# EasyEda_Node.net
KiCad netlist of a schematic drawn in EasyEDA Pro
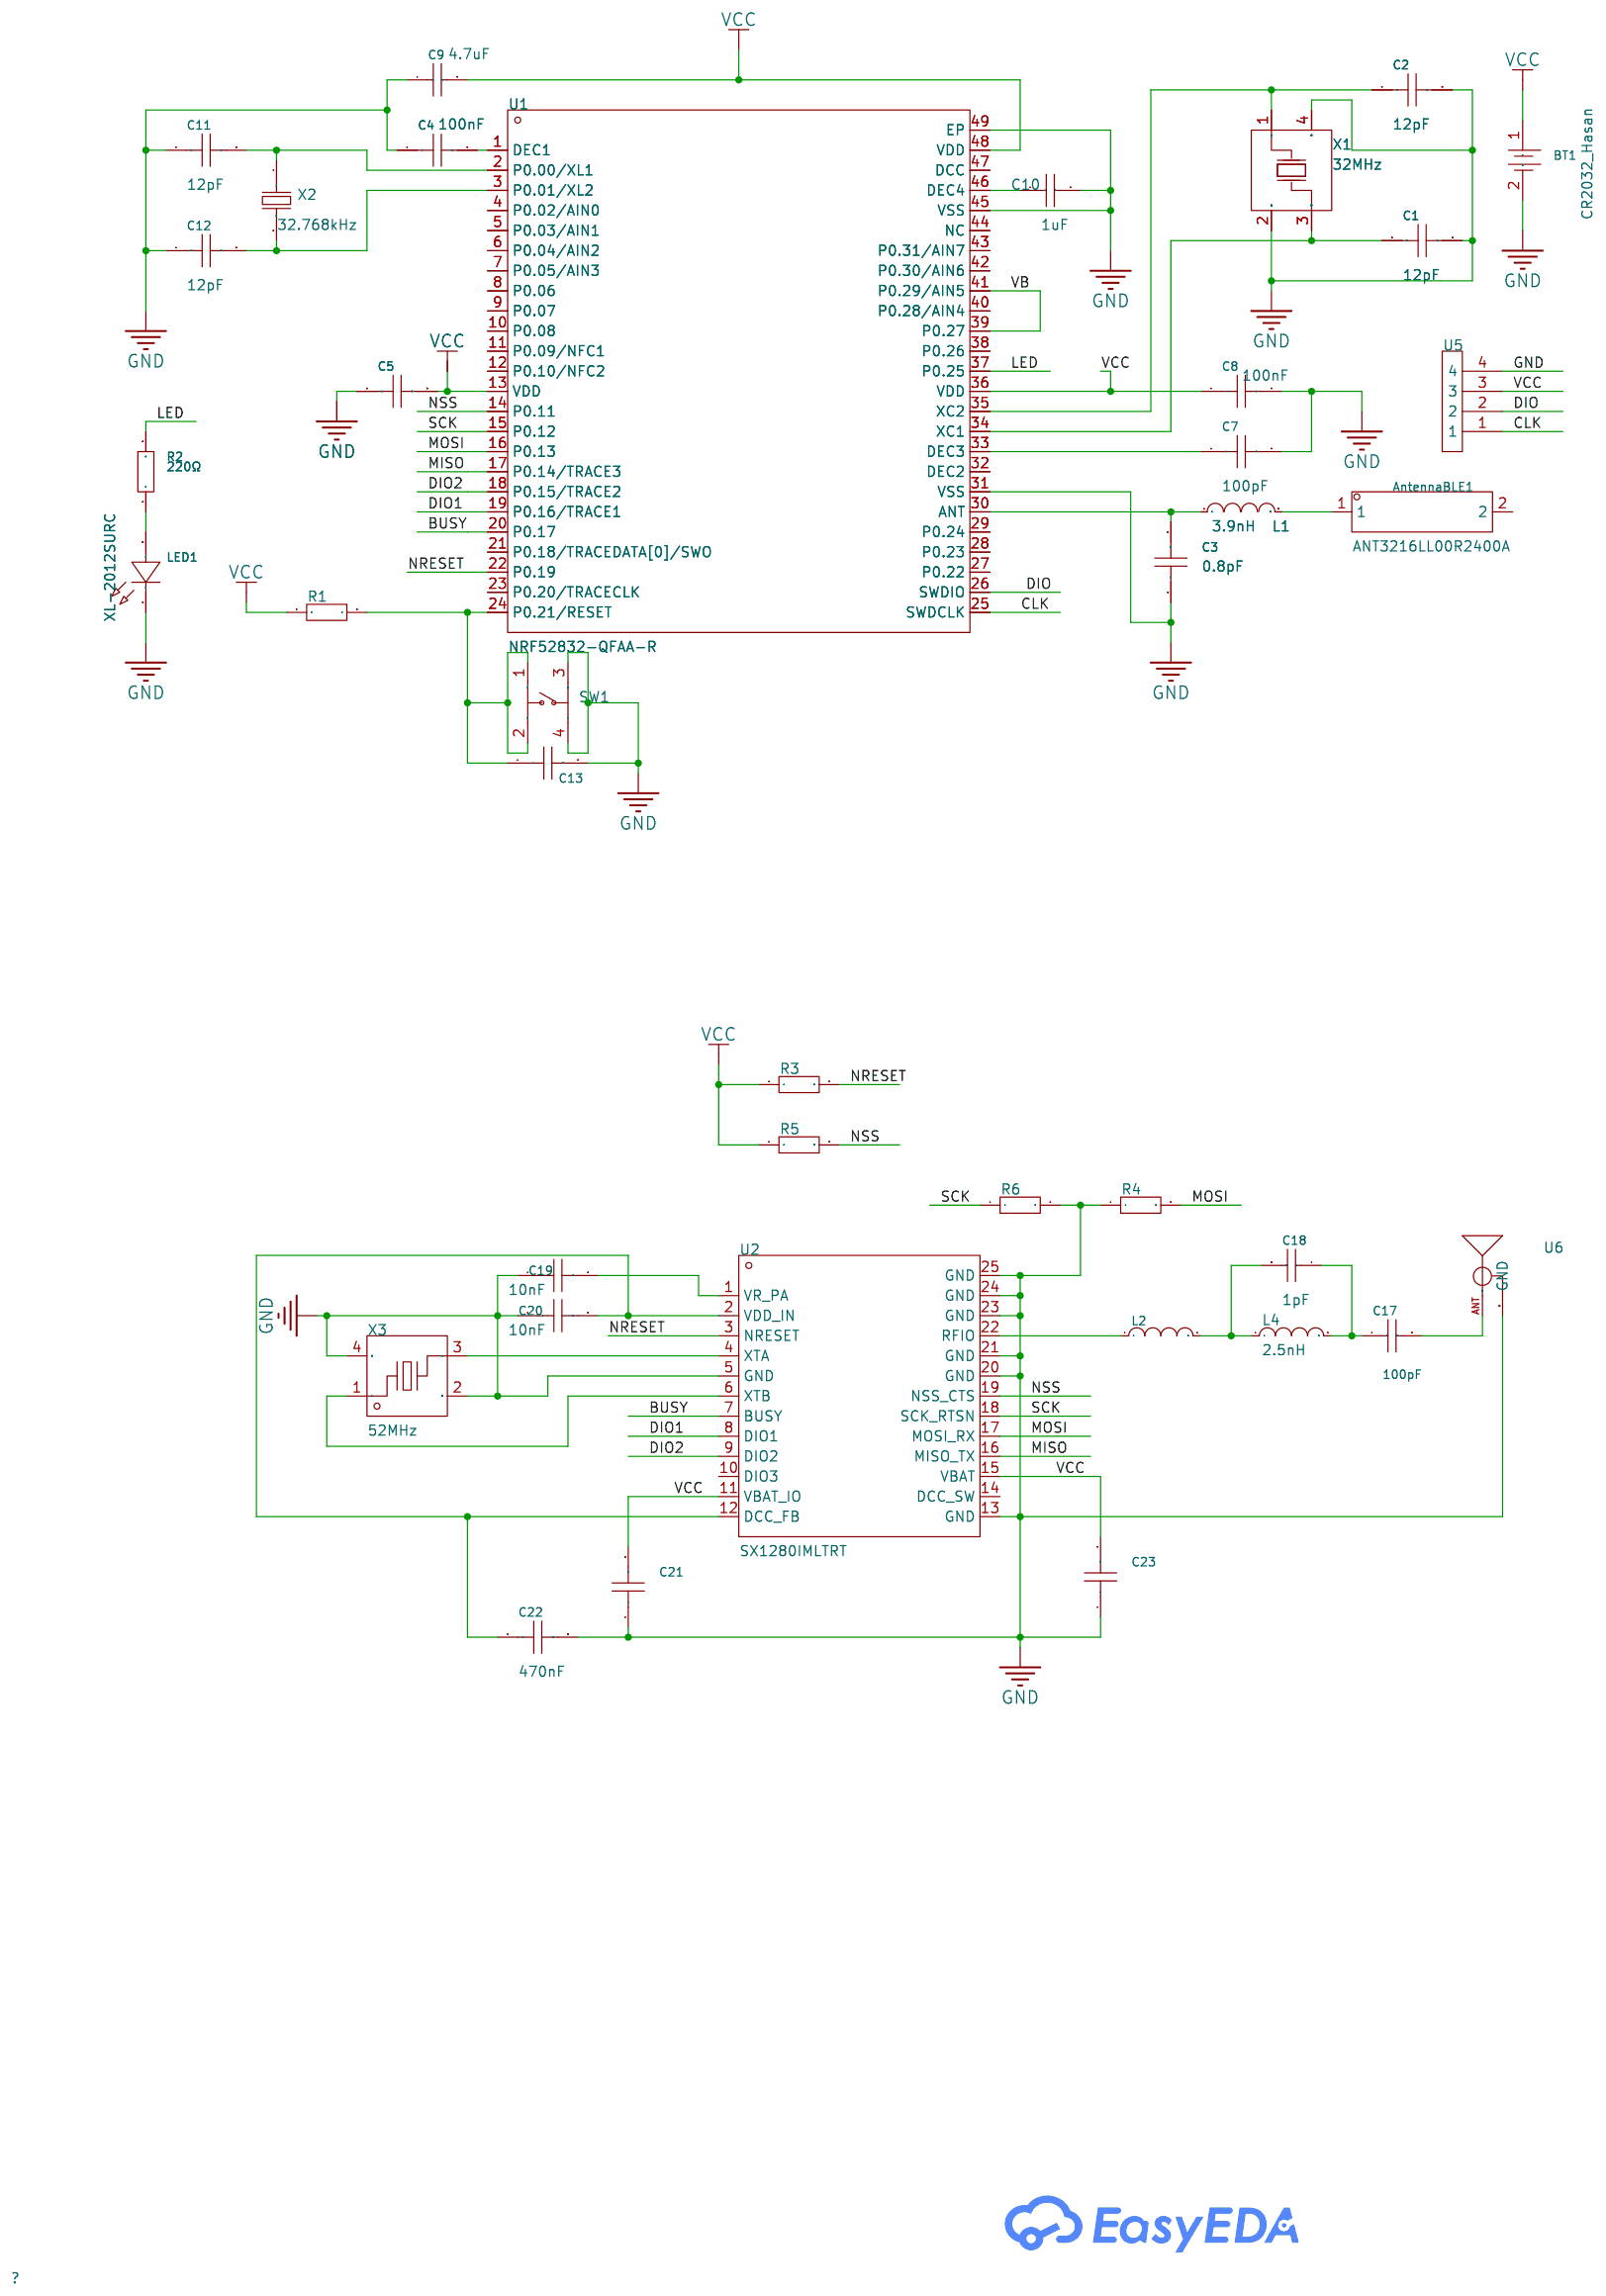
[diagram p0: schematic sheet]

(export (version "E")
  (design (tool "Eeschema 10.0.6"))
  (components
    (comp (ref "AntennaBLE1")
      (value "ANT3216LL00R2400A")
      (footprint "easyedapro:ANT-SMD_L3.2-W1.6")
      (fields (field (name "Manufacturer") "YAGEO(国巨)"))
      (libsource (lib "easyedapro") (part "ANT3216LL00R2400A"))
    )
    (comp (ref "BT1")
      (value "CR2032_Hasan")
      (fields (field (name "Manufacturer") "Q&amp;J"))
      (libsource (lib "easyedapro") (part "C70373"))
    )
    (comp (ref "C1")
      (value "12pF")
      (footprint "easyedapro:C0603")
      (fields
        (field (name "Manufacturer Part") "CC0603FRNPO9BN120")
        (field (name "Manufacturer") "YAGEO(国巨)")
      )
      (libsource (lib "easyedapro") (part "CC0603FRNPO9BN120"))
    )
    (comp (ref "C2")
      (value "12pF")
      (footprint "easyedapro:C0603")
      (fields
        (field (name "Manufacturer Part") "CC0603FRNPO9BN120")
        (field (name "Manufacturer") "YAGEO(国巨)")
      )
      (libsource (lib "easyedapro") (part "CC0603FRNPO9BN120"))
    )
    (comp (ref "C3")
      (value "0.8pF")
      (footprint "easyedapro:C0603")
      (fields
        (field (name "Manufacturer Part") "CC0603CRNPO9BNR80")
        (field (name "Manufacturer") "YAGEO(国巨)")
      )
      (libsource (lib "easyedapro") (part "CC0603CRNPO9BNR80"))
    )
    (comp (ref "C4")
      (value "100nF")
      (footprint "easyedapro:C0603")
      (fields
        (field (name "Manufacturer Part") "CL10B104KB8NNNC")
        (field (name "Manufacturer") "SAMSUNG(三星)")
      )
      (libsource (lib "easyedapro") (part "CL10B104KB8NNNC"))
    )
    (comp (ref "C5")
      (value "100nF")
      (footprint "easyedapro:C0603")
      (fields
        (field (name "Manufacturer Part") "CC0402KRX7R7BB104")
        (field (name "Manufacturer") "YAGEO(国巨)")
      )
      (libsource (lib "easyedapro") (part "CL10B104KB8NNNC"))
    )
    (comp (ref "C7")
      (value "100pF")
      (footprint "easyedapro:C0603")
      (fields
        (field (name "Manufacturer Part") "CC0603JRNPO9BN101")
        (field (name "Manufacturer") "YAGEO(国巨)")
      )
      (libsource (lib "easyedapro") (part "CC0603JRNPO9BN101"))
    )
    (comp (ref "C8")
      (value "100nF")
      (footprint "easyedapro:C0603")
      (fields
        (field (name "Manufacturer Part") "CL10B104KB8NNNC")
        (field (name "Manufacturer") "SAMSUNG(三星)")
      )
      (libsource (lib "easyedapro") (part "CL10B104KB8NNNC"))
    )
    (comp (ref "C9")
      (value "4.7uF")
      (footprint "easyedapro:C0603")
      (fields
        (field (name "Manufacturer Part") "CL10A475KP8NNNC")
        (field (name "Manufacturer") "SAMSUNG(三星)")
      )
      (libsource (lib "easyedapro") (part "CL10A475KP8NNNC"))
    )
    (comp (ref "C10")
      (value "1uF")
      (footprint "easyedapro:C0603")
      (fields
        (field (name "Manufacturer Part") "CL10A105KO8NNNC")
        (field (name "Manufacturer") "SAMSUNG(三星)")
      )
      (libsource (lib "easyedapro") (part "CL10A105KO8NNNC"))
    )
    (comp (ref "C11")
      (value "12pF")
      (footprint "easyedapro:C0603")
      (fields
        (field (name "Manufacturer Part") "CC0603FRNPO9BN120")
        (field (name "Manufacturer") "YAGEO(国巨)")
      )
      (libsource (lib "easyedapro") (part "CC0603FRNPO9BN120"))
    )
    (comp (ref "C12")
      (value "12pF")
      (footprint "easyedapro:C0603")
      (fields
        (field (name "Manufacturer Part") "CC0603FRNPO9BN120")
        (field (name "Manufacturer") "YAGEO(国巨)")
      )
      (libsource (lib "easyedapro") (part "CC0603FRNPO9BN120"))
    )
    (comp (ref "C13")
      (value "100nF")
      (footprint "easyedapro:C0603")
      (fields
        (field (name "Manufacturer Part") "CC0402KRX7R7BB104")
        (field (name "Manufacturer") "YAGEO(国巨)")
      )
      (libsource (lib "easyedapro") (part "CL10B104KB8NNNC"))
    )
    (comp (ref "C17")
      (value "100pF")
      (footprint "easyedapro:C0402")
      (fields
        (field (name "Manufacturer Part") "GRM1555C1H101JA01D")
        (field (name "Manufacturer") "muRata(村田)")
      )
      (libsource (lib "easyedapro") (part "GRM1555C1H101JA01D"))
    )
    (comp (ref "C18")
      (value "1pF")
      (footprint "easyedapro:C0402")
      (fields
        (field (name "Manufacturer Part") "GJM1555C1H1R0WB01D")
        (field (name "Manufacturer") "muRata(村田)")
      )
      (libsource (lib "easyedapro") (part "GJM1555C1H1R0WB01D"))
    )
    (comp (ref "C19")
      (value "10nF")
      (footprint "easyedapro:C0402")
      (fields
        (field (name "Manufacturer Part") "GRM155R71E103KA01D")
        (field (name "Manufacturer") "muRata(村田)")
      )
      (libsource (lib "easyedapro") (part "GRM155R71E103KA01D"))
    )
    (comp (ref "C20")
      (value "10nF")
      (footprint "easyedapro:C0402")
      (fields
        (field (name "Manufacturer Part") "GRM155R71E103KA01D")
        (field (name "Manufacturer") "muRata(村田)")
      )
      (libsource (lib "easyedapro") (part "GRM155R71E103KA01D"))
    )
    (comp (ref "C21")
      (value "100nF")
      (footprint "easyedapro:C0603")
      (fields
        (field (name "Manufacturer Part") "CC0402KRX7R7BB104")
        (field (name "Manufacturer") "YAGEO(国巨)")
      )
      (libsource (lib "easyedapro") (part "CL10B104KB8NNNC"))
    )
    (comp (ref "C22")
      (value "470nF")
      (footprint "easyedapro:C0402")
      (fields
        (field (name "Manufacturer Part") "GRM155R61A474KE15D")
        (field (name "Manufacturer") "muRata(村田)")
      )
      (libsource (lib "easyedapro") (part "GRM155R61A474KE15D"))
    )
    (comp (ref "C23")
      (value "100nF")
      (footprint "easyedapro:C0603")
      (fields
        (field (name "Manufacturer Part") "CC0402KRX7R7BB104")
        (field (name "Manufacturer") "YAGEO(国巨)")
      )
      (libsource (lib "easyedapro") (part "CL10B104KB8NNNC"))
    )
    (comp (ref "L1")
      (value "3.9nH")
      (footprint "easyedapro:L0402-RD")
      (fields
        (field (name "Manufacturer Part") "SDCL1005C3N9STDFM02")
        (field (name "Manufacturer") "Sunlord(顺络)")
      )
      (libsource (lib "easyedapro") (part "SDCL1005C3N9STDFM02"))
    )
    (comp (ref "L2")
      (value "3nH")
      (footprint "easyedapro:L0402")
      (description "Inductance:3nH Rated Current: Saturation Current (Isat):- DC Resistance (DCR): Ratings:-")
      (fields (field (name "Manufacturer Part") "LQW15AN3N0B80D") (field (name "Manufacturer") "muRata(村田)"))
      (libsource (lib "easyedapro") (part "LQW15AN3N0B80D"))
    )
    (comp (ref "L4")
      (value "2.5nH")
      (footprint "easyedapro:L0402")
      (description "Inductance:2.5nH Rated Current: Saturation Current (Isat):- DC Resistance (DCR): Ratings:-")
      (fields (field (name "Manufacturer Part") "LQW15AN2N5C00D") (field (name "Manufacturer") "muRata(村田)"))
      (libsource (lib "easyedapro") (part "LQW15AN2N5C00D"))
    )
    (comp (ref "LED1")
      (value "XL-2012SURC")
      (footprint "easyedapro:LED0805-RD_RED")
      (fields (field (name "Manufacturer") "XINGLIGHT(成兴光)"))
      (libsource (lib "easyedapro") (part "XL-2012SURC"))
    )
    (comp (ref "R1")
      (value "10kΩ")
      (fields (field (name "Manufacturer Part") "RC0402FR-0710KL") (field (name "Manufacturer") "YAGEO(国巨)"))
      (libsource (lib "easyedapro") (part "RC0603FR-0710KL"))
    )
    (comp (ref "R2")
      (value "220Ω")
      (footprint "easyedapro:R0603")
      (fields
        (field (name "Manufacturer Part") "0603WAF2200T5E")
        (field (name "Manufacturer") "UNI-ROYAL(厚声)")
      )
      (libsource (lib "easyedapro") (part "0603WAF2200T5E"))
    )
    (comp (ref "R3")
      (value "10kΩ")
      (fields (field (name "Manufacturer Part") "RC0402FR-0710KL") (field (name "Manufacturer") "YAGEO(国巨)"))
      (libsource (lib "easyedapro") (part "RC0603FR-0710KL"))
    )
    (comp (ref "R4")
      (value "10kΩ")
      (fields (field (name "Manufacturer Part") "RC0402FR-0710KL") (field (name "Manufacturer") "YAGEO(国巨)"))
      (libsource (lib "easyedapro") (part "RC0603FR-0710KL"))
    )
    (comp (ref "R5")
      (value "10kΩ")
      (fields (field (name "Manufacturer Part") "RC0402FR-0710KL") (field (name "Manufacturer") "YAGEO(国巨)"))
      (libsource (lib "easyedapro") (part "RC0603FR-0710KL"))
    )
    (comp (ref "R6")
      (value "10kΩ")
      (fields (field (name "Manufacturer Part") "RC0402FR-0710KL") (field (name "Manufacturer") "YAGEO(国巨)"))
      (libsource (lib "easyedapro") (part "RC0603FR-0710KL"))
    )
    (comp (ref "SW1")
      (value "1TS026A-2300-0553-CT")
      (footprint "easyedapro:SW-SMD_4P-L2.6-W1.6-P0.75-LS3.0")
      (fields (field (name "Manufacturer") "HYP(鸿源精密)"))
      (libsource (lib "easyedapro") (part "1TS026A-2300-0553-CT"))
    )
    (comp (ref "U1")
      (value "NRF52832-QFAA-R")
      (footprint "easyedapro:QFN-48_L6.0-W6.0-P0.40-BL-EP3.8")
      (fields (field (name "Manufacturer") "NORDIC"))
      (libsource (lib "easyedapro") (part "NRF52832-QFAA-R"))
    )
    (comp (ref "U2")
      (value "SX1280IMLTRT")
      (footprint "easyedapro:QFN-24_L4.0-W4.0-P0.50-BL-EP2.6")
      (fields (field (name "Manufacturer") "SEMTECH"))
      (libsource (lib "easyedapro") (part "SX1280IMLTRT"))
    )
    (comp (ref "U5")
      (value "~")
      (footprint "easyedapro:pogo_4p_passive_1.27")
      (libsource (lib "easyedapro") (part "pogo_4p_passive_1.27"))
    )
    (comp (ref "U6")
      (value "~")
      (footprint "easyedapro:Init_antenna_Taobao")
      (description "2.4 GHz Init")
      (libsource (lib "easyedapro") (part "Init_antenna_Taobao"))
    )
    (comp (ref "X1")
      (value "32MHz")
      (footprint "easyedapro:CRYSTAL-SMD_4P-L3.2-W2.5-BL")
      (fields (field (name "Manufacturer Part") "X322532MOB4SI") (field (name "Manufacturer") "YXC(扬兴晶振)"))
      (libsource (lib "easyedapro") (part "X322532MOB4SI"))
    )
    (comp (ref "X2")
      (value "32.768kHz")
      (footprint "easyedapro:CRYSTAL-SMD_L3.2-W1.5")
      (fields
        (field (name "Manufacturer Part") "FC31M2-32.768-NTLNNDTL")
        (field (name "Manufacturer") "HCI(杭晶)")
      )
      (libsource (lib "easyedapro") (part "FC31M2-32.768-NTLNNDTL"))
    )
    (comp (ref "X3")
      (value "52MHz")
      (footprint "easyedapro:CRYSTAL-SMD_4P-L3.2-W2.5-BL")
      (fields
        (field (name "Manufacturer Part") "SX3B52.000F1010F30")
        (field (name "Manufacturer") "SCTF(星通时频)")
      )
      (libsource (lib "easyedapro") (part "SX3B52.000F1010F30"))
    )
  )
  (nets
    (net (code "1") (name "/BUSY") (class "Default")
      (node (ref "U1") (pin "20") (pinfunction "P0.17_20") (pintype "unspecified"))
      (node (ref "U2") (pin "7") (pinfunction "BUSY_7") (pintype "input"))
    )
    (net (code "2") (name "/CLK") (class "Default")
      (node (ref "U1") (pin "25") (pinfunction "SWDCLK_25") (pintype "unspecified"))
      (node (ref "U5") (pin "1") (pinfunction "1_1") (pintype "input"))
    )
    (net (code "3") (name "/DIO") (class "Default")
      (node (ref "U1") (pin "26") (pinfunction "SWDIO_26") (pintype "unspecified"))
      (node (ref "U5") (pin "2") (pinfunction "2_2") (pintype "input"))
    )
    (net (code "4") (name "/DIO1") (class "Default")
      (node (ref "U1") (pin "19") (pinfunction "P0.16/TRACE1_19") (pintype "unspecified"))
      (node (ref "U2") (pin "8") (pinfunction "DIO1_8") (pintype "input"))
    )
    (net (code "5") (name "/DIO2") (class "Default")
      (node (ref "U1") (pin "18") (pinfunction "P0.15/TRACE2_18") (pintype "unspecified"))
      (node (ref "U2") (pin "9") (pinfunction "DIO2_9") (pintype "input"))
    )
    (net (code "6") (name "/LED") (class "Default")
      (node (ref "R2") (pin "2") (pinfunction "2_2") (pintype "input"))
      (node (ref "U1") (pin "37") (pinfunction "P0.25_37") (pintype "unspecified"))
    )
    (net (code "7") (name "/MISO") (class "Default")
      (node (ref "U1") (pin "17") (pinfunction "P0.14/TRACE3_17") (pintype "unspecified"))
      (node (ref "U2") (pin "16") (pinfunction "MISO_TX_16") (pintype "input"))
    )
    (net (code "8") (name "/MOSI") (class "Default")
      (node (ref "R4") (pin "2") (pinfunction "2_2") (pintype "input"))
      (node (ref "U1") (pin "16") (pinfunction "P0.13_16") (pintype "unspecified"))
      (node (ref "U2") (pin "17") (pinfunction "MOSI_RX_17") (pintype "input"))
    )
    (net (code "9") (name "/NRESET") (class "Default")
      (node (ref "R3") (pin "2") (pinfunction "2_2") (pintype "input"))
      (node (ref "U1") (pin "22") (pinfunction "P0.19_22") (pintype "unspecified"))
      (node (ref "U2") (pin "3") (pinfunction "NRESET_3") (pintype "input"))
    )
    (net (code "10") (name "/NSS") (class "Default")
      (node (ref "R5") (pin "2") (pinfunction "2_2") (pintype "input"))
      (node (ref "U1") (pin "14") (pinfunction "P0.11_14") (pintype "unspecified"))
      (node (ref "U2") (pin "19") (pinfunction "NSS_CTS_19") (pintype "input"))
    )
    (net (code "11") (name "/SCK") (class "Default")
      (node (ref "R6") (pin "1") (pinfunction "1_1") (pintype "input"))
      (node (ref "U1") (pin "15") (pinfunction "P0.12_15") (pintype "unspecified"))
      (node (ref "U2") (pin "18") (pinfunction "SCK_RTSN_18") (pintype "input"))
    )
    (net (code "12") (name "/VB") (class "Default")
      (node (ref "U1") (pin "39") (pinfunction "P0.27_39") (pintype "unspecified"))
      (node (ref "U1") (pin "41") (pinfunction "P0.29/AIN5_41") (pintype "unspecified"))
    )
    (net (code "13") (name "GND") (class "Default")
      (node (ref "BT1") (pin "2") (pinfunction "2_2") (pintype "input"))
      (node (ref "C1") (pin "2") (pinfunction "2_2") (pintype "input"))
      (node (ref "C10") (pin "2") (pinfunction "2_2") (pintype "input"))
      (node (ref "C11") (pin "1") (pinfunction "1_1") (pintype "input"))
      (node (ref "C12") (pin "1") (pinfunction "1_1") (pintype "input"))
      (node (ref "C13") (pin "2") (pinfunction "2_2") (pintype "input"))
      (node (ref "C19") (pin "1") (pinfunction "1_1") (pintype "input"))
      (node (ref "C2") (pin "2") (pinfunction "2_2") (pintype "input"))
      (node (ref "C20") (pin "1") (pinfunction "1_1") (pintype "input"))
      (node (ref "C21") (pin "1") (pinfunction "1_1") (pintype "input"))
      (node (ref "C22") (pin "2") (pinfunction "2_2") (pintype "input"))
      (node (ref "C23") (pin "1") (pinfunction "1_1") (pintype "input"))
      (node (ref "C3") (pin "1") (pinfunction "1_1") (pintype "input"))
      (node (ref "C4") (pin "1") (pinfunction "1_1") (pintype "input"))
      (node (ref "C5") (pin "1") (pinfunction "1_1") (pintype "input"))
      (node (ref "C7") (pin "2") (pinfunction "2_2") (pintype "input"))
      (node (ref "C8") (pin "2") (pinfunction "2_2") (pintype "input"))
      (node (ref "C9") (pin "1") (pinfunction "1_1") (pintype "input"))
      (node (ref "LED1") (pin "1") (pinfunction "K_1") (pintype "input"))
      (node (ref "R4") (pin "1") (pinfunction "1_1") (pintype "input"))
      (node (ref "R6") (pin "2") (pinfunction "2_2") (pintype "input"))
      (node (ref "SW1") (pin "3") (pinfunction "3_3") (pintype "input"))
      (node (ref "SW1") (pin "4") (pinfunction "4_4") (pintype "input"))
      (node (ref "U1") (pin "31") (pinfunction "VSS_31") (pintype "unspecified"))
      (node (ref "U1") (pin "45") (pinfunction "VSS_45") (pintype "unspecified"))
      (node (ref "U1") (pin "49") (pinfunction "EP_49") (pintype "unspecified"))
      (node (ref "U2") (pin "13") (pinfunction "GND_13") (pintype "input"))
      (node (ref "U2") (pin "20") (pinfunction "GND_20") (pintype "input"))
      (node (ref "U2") (pin "21") (pinfunction "GND_21") (pintype "input"))
      (node (ref "U2") (pin "23") (pinfunction "GND_23") (pintype "input"))
      (node (ref "U2") (pin "24") (pinfunction "GND_24") (pintype "input"))
      (node (ref "U2") (pin "25") (pinfunction "GND_25") (pintype "input"))
      (node (ref "U2") (pin "5") (pinfunction "GND_5") (pintype "input"))
      (node (ref "U5") (pin "4") (pinfunction "4_4") (pintype "input"))
      (node (ref "U6") (pin "GND") (pinfunction "GND_GND") (pintype "bidirectional"))
      (node (ref "X1") (pin "2") (pinfunction "GND_2") (pintype "unspecified"))
      (node (ref "X1") (pin "4") (pinfunction "GND_4") (pintype "unspecified"))
      (node (ref "X3") (pin "2") (pinfunction "GND_2") (pintype "input"))
      (node (ref "X3") (pin "4") (pinfunction "GND_4") (pintype "input"))
    )
    (net (code "14") (name "Net-(AntennaBLE1-Pad1)") (class "Default")
      (node (ref "AntennaBLE1") (pin "1") (pinfunction "1_1") (pintype "input"))
      (node (ref "L1") (pin "2") (pinfunction "2_2") (pintype "input"))
    )
    (net (code "15") (name "Net-(C17-Pad1)") (class "Default")
      (node (ref "C17") (pin "1") (pinfunction "1_1") (pintype "input"))
      (node (ref "C18") (pin "1") (pinfunction "1_1") (pintype "input"))
      (node (ref "L4") (pin "2") (pinfunction "2_2") (pintype "unspecified"))
    )
    (net (code "16") (name "Net-(C18-Pad2)") (class "Default")
      (node (ref "C18") (pin "2") (pinfunction "2_2") (pintype "input"))
      (node (ref "L2") (pin "2") (pinfunction "2_2") (pintype "unspecified"))
      (node (ref "L4") (pin "1") (pinfunction "1_1") (pintype "unspecified"))
    )
    (net (code "17") (name "Net-(LED1-A)") (class "Default")
      (node (ref "LED1") (pin "2") (pinfunction "A_2") (pintype "input"))
      (node (ref "R2") (pin "1") (pinfunction "1_1") (pintype "input"))
    )
    (net (code "18") (name "Net-(U1-ANT)") (class "Default")
      (node (ref "C3") (pin "2") (pinfunction "2_2") (pintype "input"))
      (node (ref "L1") (pin "1") (pinfunction "1_1") (pintype "input"))
      (node (ref "U1") (pin "30") (pinfunction "ANT_30") (pintype "unspecified"))
    )
    (net (code "19") (name "Net-(U1-DEC1)") (class "Default")
      (node (ref "C4") (pin "2") (pinfunction "2_2") (pintype "input"))
      (node (ref "U1") (pin "1") (pinfunction "DEC1_1") (pintype "unspecified"))
    )
    (net (code "20") (name "Net-(U1-DEC3)") (class "Default")
      (node (ref "C7") (pin "1") (pinfunction "1_1") (pintype "input"))
      (node (ref "U1") (pin "33") (pinfunction "DEC3_33") (pintype "unspecified"))
    )
    (net (code "21") (name "Net-(U1-DEC4)") (class "Default")
      (node (ref "C10") (pin "1") (pinfunction "1_1") (pintype "input"))
      (node (ref "U1") (pin "46") (pinfunction "DEC4_46") (pintype "unspecified"))
    )
    (net (code "22") (name "Net-(U1-P0.00{slash}XL1)") (class "Default")
      (node (ref "C11") (pin "2") (pinfunction "2_2") (pintype "input"))
      (node (ref "U1") (pin "2") (pinfunction "P0.00/XL1_2") (pintype "unspecified"))
      (node (ref "X2") (pin "1") (pinfunction "1_1") (pintype "unspecified"))
    )
    (net (code "23") (name "Net-(U1-P0.01{slash}XL2)") (class "Default")
      (node (ref "C12") (pin "2") (pinfunction "2_2") (pintype "input"))
      (node (ref "U1") (pin "3") (pinfunction "P0.01/XL2_3") (pintype "unspecified"))
      (node (ref "X2") (pin "2") (pinfunction "2_2") (pintype "unspecified"))
    )
    (net (code "24") (name "Net-(U1-P0.21{slash}RESET)") (class "Default")
      (node (ref "C13") (pin "1") (pinfunction "1_1") (pintype "input"))
      (node (ref "R1") (pin "2") (pinfunction "2_2") (pintype "input"))
      (node (ref "SW1") (pin "1") (pinfunction "1_1") (pintype "input"))
      (node (ref "SW1") (pin "2") (pinfunction "2_2") (pintype "input"))
      (node (ref "U1") (pin "24") (pinfunction "P0.21/RESET_24") (pintype "unspecified"))
    )
    (net (code "25") (name "Net-(U1-XC1)") (class "Default")
      (node (ref "C1") (pin "1") (pinfunction "1_1") (pintype "input"))
      (node (ref "U1") (pin "34") (pinfunction "XC1_34") (pintype "unspecified"))
      (node (ref "X1") (pin "3") (pinfunction "OSC2_3") (pintype "unspecified"))
    )
    (net (code "26") (name "Net-(U1-XC2)") (class "Default")
      (node (ref "C2") (pin "1") (pinfunction "1_1") (pintype "input"))
      (node (ref "U1") (pin "35") (pinfunction "XC2_35") (pintype "unspecified"))
      (node (ref "X1") (pin "1") (pinfunction "OSC1_1") (pintype "unspecified"))
    )
    (net (code "27") (name "Net-(U2-DCC_FB)") (class "Default")
      (node (ref "C20") (pin "2") (pinfunction "2_2") (pintype "input"))
      (node (ref "C22") (pin "1") (pinfunction "1_1") (pintype "input"))
      (node (ref "U2") (pin "12") (pinfunction "DCC_FB_12") (pintype "input"))
      (node (ref "U2") (pin "2") (pinfunction "VDD_IN_2") (pintype "input"))
    )
    (net (code "28") (name "Net-(U2-RFIO)") (class "Default")
      (node (ref "L2") (pin "1") (pinfunction "1_1") (pintype "unspecified"))
      (node (ref "U2") (pin "22") (pinfunction "RFIO_22") (pintype "input"))
    )
    (net (code "29") (name "Net-(U2-VR_PA)") (class "Default")
      (node (ref "C19") (pin "2") (pinfunction "2_2") (pintype "input"))
      (node (ref "U2") (pin "1") (pinfunction "VR_PA_1") (pintype "input"))
    )
    (net (code "30") (name "Net-(U2-XTA)") (class "Default")
      (node (ref "U2") (pin "4") (pinfunction "XTA_4") (pintype "input"))
      (node (ref "X3") (pin "3") (pinfunction "3_3") (pintype "input"))
    )
    (net (code "31") (name "Net-(U2-XTB)") (class "Default")
      (node (ref "U2") (pin "6") (pinfunction "XTB_6") (pintype "input"))
      (node (ref "X3") (pin "1") (pinfunction "1_1") (pintype "input"))
    )
    (net (code "32") (name "Net-(U6-SIGNAL)") (class "Default")
      (node (ref "C17") (pin "2") (pinfunction "2_2") (pintype "input"))
      (node (ref "U6") (pin "ANT") (pinfunction "SIGNAL_ANT") (pintype "bidirectional"))
    )
    (net (code "33") (name "VCC") (class "Default")
      (node (ref "BT1") (pin "1") (pinfunction "1_1") (pintype "input"))
      (node (ref "C21") (pin "2") (pinfunction "2_2") (pintype "input"))
      (node (ref "C23") (pin "2") (pinfunction "2_2") (pintype "input"))
      (node (ref "C5") (pin "2") (pinfunction "2_2") (pintype "input"))
      (node (ref "C8") (pin "1") (pinfunction "1_1") (pintype "input"))
      (node (ref "C9") (pin "2") (pinfunction "2_2") (pintype "input"))
      (node (ref "R1") (pin "1") (pinfunction "1_1") (pintype "input"))
      (node (ref "R3") (pin "1") (pinfunction "1_1") (pintype "input"))
      (node (ref "R5") (pin "1") (pinfunction "1_1") (pintype "input"))
      (node (ref "U1") (pin "13") (pinfunction "VDD_13") (pintype "unspecified"))
      (node (ref "U1") (pin "36") (pinfunction "VDD_36") (pintype "unspecified"))
      (node (ref "U1") (pin "48") (pinfunction "VDD_48") (pintype "unspecified"))
      (node (ref "U2") (pin "11") (pinfunction "VBAT_IO_11") (pintype "input"))
      (node (ref "U2") (pin "15") (pinfunction "VBAT_15") (pintype "input"))
      (node (ref "U5") (pin "3") (pinfunction "3_3") (pintype "input"))
    )
    (net (code "34") (name "unconnected-(AntennaBLE1-Pad2)") (class "Default")
      (node (ref "AntennaBLE1") (pin "2") (pinfunction "2_2") (pintype "input"))
    )
    (net (code "35") (name "unconnected-(U1-DCC-Pad47)") (class "Default")
      (node (ref "U1") (pin "47") (pinfunction "DCC_47") (pintype "unspecified"))
    )
    (net (code "36") (name "unconnected-(U1-DEC2-Pad32)") (class "Default")
      (node (ref "U1") (pin "32") (pinfunction "DEC2_32") (pintype "unspecified"))
    )
    (net (code "37") (name "unconnected-(U1-NC-Pad44)") (class "Default")
      (node (ref "U1") (pin "44") (pinfunction "NC_44") (pintype "unspecified"))
    )
    (net (code "38") (name "unconnected-(U1-P0.02{slash}AIN0-Pad4)") (class "Default")
      (node (ref "U1") (pin "4") (pinfunction "P0.02/AIN0_4") (pintype "unspecified"))
    )
    (net (code "39") (name "unconnected-(U1-P0.03{slash}AIN1-Pad5)") (class "Default")
      (node (ref "U1") (pin "5") (pinfunction "P0.03/AIN1_5") (pintype "unspecified"))
    )
    (net (code "40") (name "unconnected-(U1-P0.04{slash}AIN2-Pad6)") (class "Default")
      (node (ref "U1") (pin "6") (pinfunction "P0.04/AIN2_6") (pintype "unspecified"))
    )
    (net (code "41") (name "unconnected-(U1-P0.05{slash}AIN3-Pad7)") (class "Default")
      (node (ref "U1") (pin "7") (pinfunction "P0.05/AIN3_7") (pintype "unspecified"))
    )
    (net (code "42") (name "unconnected-(U1-P0.06-Pad8)") (class "Default")
      (node (ref "U1") (pin "8") (pinfunction "P0.06_8") (pintype "unspecified"))
    )
    (net (code "43") (name "unconnected-(U1-P0.07-Pad9)") (class "Default")
      (node (ref "U1") (pin "9") (pinfunction "P0.07_9") (pintype "unspecified"))
    )
    (net (code "44") (name "unconnected-(U1-P0.08-Pad10)") (class "Default")
      (node (ref "U1") (pin "10") (pinfunction "P0.08_10") (pintype "unspecified"))
    )
    (net (code "45") (name "unconnected-(U1-P0.09{slash}NFC1-Pad11)") (class "Default")
      (node (ref "U1") (pin "11") (pinfunction "P0.09/NFC1_11") (pintype "unspecified"))
    )
    (net (code "46") (name "unconnected-(U1-P0.10{slash}NFC2-Pad12)") (class "Default")
      (node (ref "U1") (pin "12") (pinfunction "P0.10/NFC2_12") (pintype "unspecified"))
    )
    (net (code "47") (name "unconnected-(U1-P0.18{slash}TRACEDATA[0]{slash}SWO-Pad21)") (class "Default")
      (node (ref "U1") (pin "21") (pinfunction "P0.18/TRACEDATA[0]/SWO_21") (pintype "unspecified"))
    )
    (net (code "48") (name "unconnected-(U1-P0.20{slash}TRACECLK-Pad23)") (class "Default")
      (node (ref "U1") (pin "23") (pinfunction "P0.20/TRACECLK_23") (pintype "unspecified"))
    )
    (net (code "49") (name "unconnected-(U1-P0.22-Pad27)") (class "Default")
      (node (ref "U1") (pin "27") (pinfunction "P0.22_27") (pintype "unspecified"))
    )
    (net (code "50") (name "unconnected-(U1-P0.23-Pad28)") (class "Default")
      (node (ref "U1") (pin "28") (pinfunction "P0.23_28") (pintype "unspecified"))
    )
    (net (code "51") (name "unconnected-(U1-P0.24-Pad29)") (class "Default")
      (node (ref "U1") (pin "29") (pinfunction "P0.24_29") (pintype "unspecified"))
    )
    (net (code "52") (name "unconnected-(U1-P0.26-Pad38)") (class "Default")
      (node (ref "U1") (pin "38") (pinfunction "P0.26_38") (pintype "unspecified"))
    )
    (net (code "53") (name "unconnected-(U1-P0.28{slash}AIN4-Pad40)") (class "Default")
      (node (ref "U1") (pin "40") (pinfunction "P0.28/AIN4_40") (pintype "unspecified"))
    )
    (net (code "54") (name "unconnected-(U1-P0.30{slash}AIN6-Pad42)") (class "Default")
      (node (ref "U1") (pin "42") (pinfunction "P0.30/AIN6_42") (pintype "unspecified"))
    )
    (net (code "55") (name "unconnected-(U1-P0.31{slash}AIN7-Pad43)") (class "Default")
      (node (ref "U1") (pin "43") (pinfunction "P0.31/AIN7_43") (pintype "unspecified"))
    )
    (net (code "56") (name "unconnected-(U2-DCC_SW-Pad14)") (class "Default")
      (node (ref "U2") (pin "14") (pinfunction "DCC_SW_14") (pintype "input"))
    )
    (net (code "57") (name "unconnected-(U2-DIO3-Pad10)") (class "Default")
      (node (ref "U2") (pin "10") (pinfunction "DIO3_10") (pintype "input"))
    )
  )
)
